# beacon.net
KiCad netlist of a schematic drawn in EAGLE
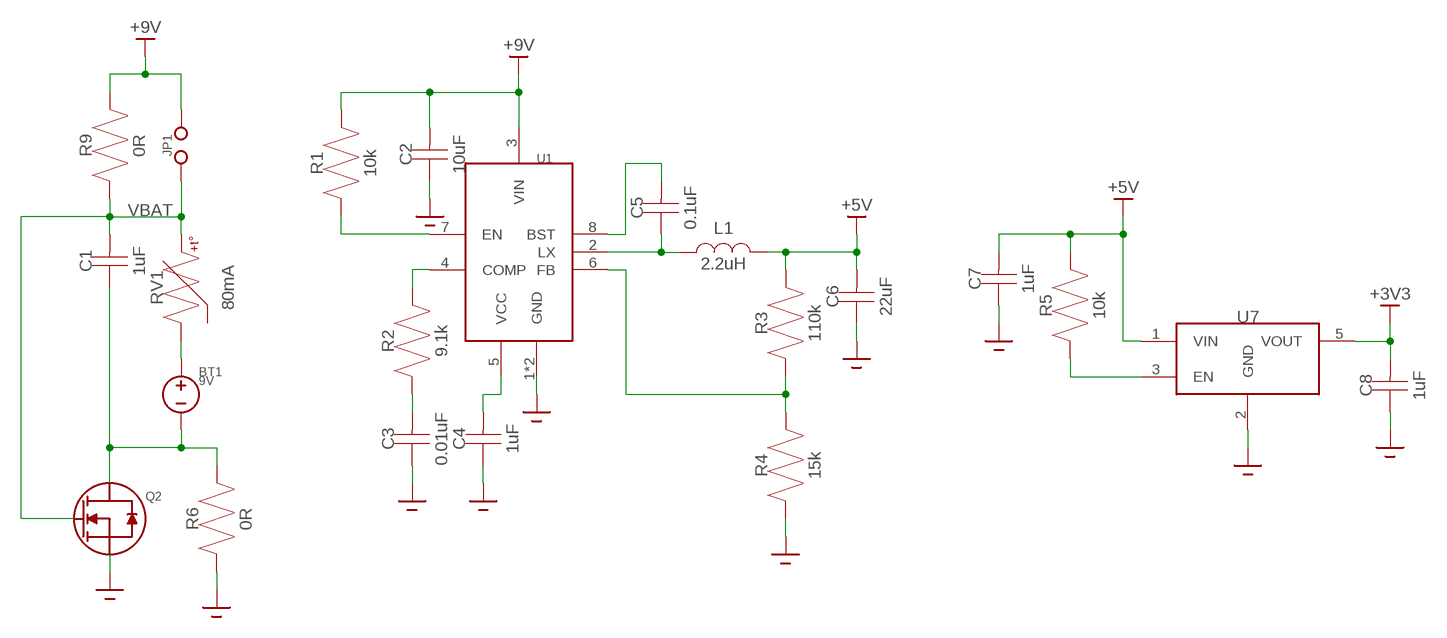
[diagram p0: schematic, sheet 1]
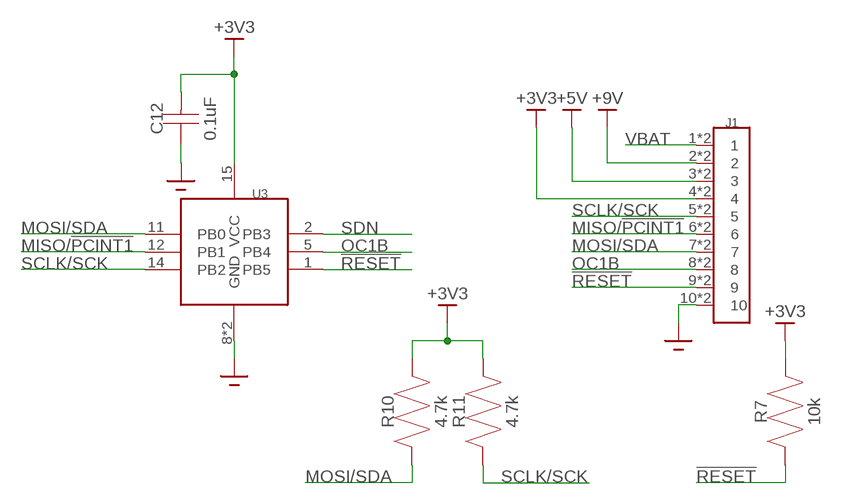
[diagram p1: schematic, sheet 2]
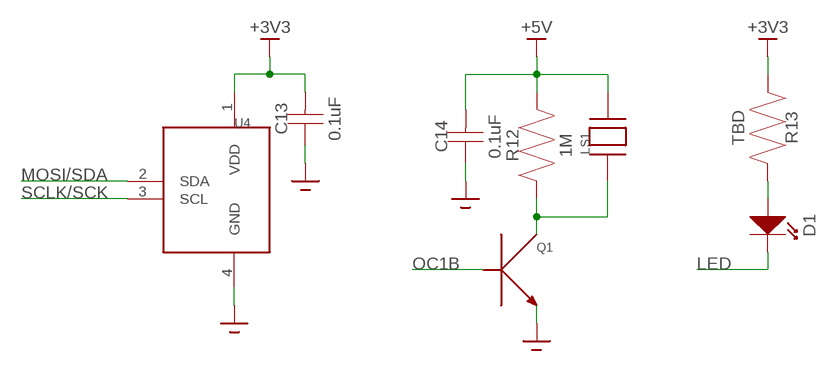
[diagram p2: schematic, sheet 3]
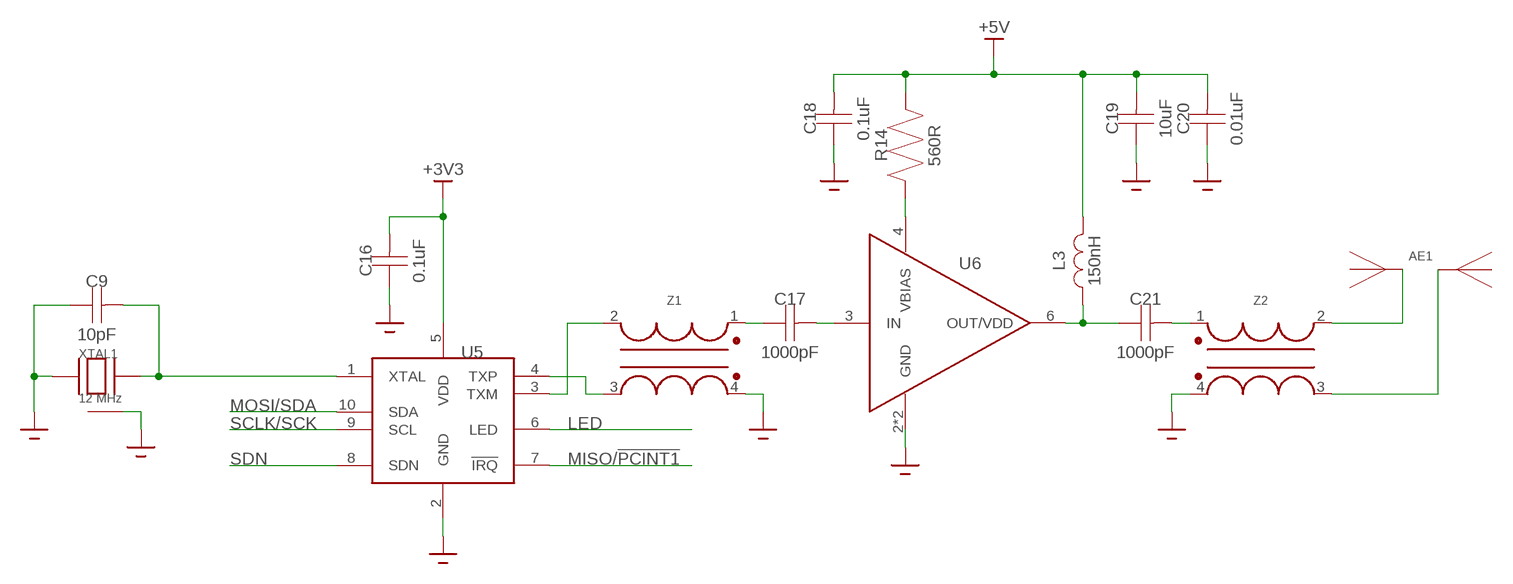
[diagram p3: schematic, sheet 4]

(export (version "E")
  (design (tool "Eeschema 10.0.6"))
  (components
    (comp (ref "AE1")
      (value "ANTENNA")
      (footprint "eagle-import:ANTENNA")
      (libsource (lib "eagle-import") (part "ANTENNA"))
    )
    (comp (ref "C9")
      (value "10pF")
      (footprint "eagle-import:0603")
      (libsource (lib "eagle-import") (part "CAPACITOR0603"))
    )
    (comp (ref "C16")
      (value "0.1uF")
      (footprint "eagle-import:0603")
      (libsource (lib "eagle-import") (part "CAPACITOR0603"))
    )
    (comp (ref "C17")
      (value "1000pF")
      (footprint "eagle-import:0402")
      (libsource (lib "eagle-import") (part "CAPACITOR0402"))
    )
    (comp (ref "C18")
      (value "0.1uF")
      (footprint "eagle-import:0603")
      (libsource (lib "eagle-import") (part "CAPACITOR0603"))
    )
    (comp (ref "C19")
      (value "10uF")
      (footprint "eagle-import:0603")
      (libsource (lib "eagle-import") (part "CAPACITOR0603"))
    )
    (comp (ref "C20")
      (value "0.01uF")
      (footprint "eagle-import:0603")
      (libsource (lib "eagle-import") (part "CAPACITOR0603"))
    )
    (comp (ref "C21")
      (value "1000pF")
      (footprint "eagle-import:0402")
      (libsource (lib "eagle-import") (part "CAPACITOR0402"))
    )
    (comp (ref "L3")
      (value "150nH")
      (footprint "eagle-import:0402")
      (libsource (lib "eagle-import") (part "INDUCTOR0402"))
    )
    (comp (ref "R14")
      (value "560R")
      (footprint "eagle-import:0603")
      (libsource (lib "eagle-import") (part "RESISTOR0603"))
    )
    (comp (ref "U5")
      (value "SI4012")
      (footprint "eagle-import:SI4012")
      (libsource (lib "eagle-import") (part "SI4012"))
    )
    (comp (ref "U6")
      (value "MAAL-010704")
      (footprint "eagle-import:MAAL-010704")
      (libsource (lib "eagle-import") (part "MAAL-010704"))
    )
    (comp (ref "XTAL1")
      (value "12 MHz")
      (footprint "eagle-import:RH100")
      (libsource (lib "eagle-import") (part "RH100"))
    )
    (comp (ref "Z1")
      (value "ABT-8")
      (footprint "eagle-import:ABT-8")
      (libsource (lib "eagle-import") (part "ABT-8"))
    )
    (comp (ref "Z2")
      (value "ABT-8")
      (footprint "eagle-import:ABT-8")
      (libsource (lib "eagle-import") (part "ABT-8"))
    )
    (comp (ref "BT1")
      (value "9V")
      (footprint "eagle-import:JUMPER")
      (libsource (lib "eagle-import") (part "BATTERY"))
    )
    (comp (ref "C1")
      (value "1uF")
      (footprint "eagle-import:0603")
      (libsource (lib "eagle-import") (part "CAPACITOR0603"))
    )
    (comp (ref "C2")
      (value "10uF")
      (footprint "eagle-import:0805")
      (libsource (lib "eagle-import") (part "CAPACITOR0805"))
    )
    (comp (ref "C3")
      (value "0.01uF")
      (footprint "eagle-import:0603")
      (libsource (lib "eagle-import") (part "CAPACITOR0603"))
    )
    (comp (ref "C4")
      (value "1uF")
      (footprint "eagle-import:0603")
      (libsource (lib "eagle-import") (part "CAPACITOR0603"))
    )
    (comp (ref "C5")
      (value "0.1uF")
      (footprint "eagle-import:0603")
      (libsource (lib "eagle-import") (part "CAPACITOR0603"))
    )
    (comp (ref "C6")
      (value "22uF")
      (footprint "eagle-import:0805")
      (libsource (lib "eagle-import") (part "CAPACITOR0805"))
    )
    (comp (ref "C7")
      (value "1uF")
      (footprint "eagle-import:0603")
      (libsource (lib "eagle-import") (part "CAPACITOR0603"))
    )
    (comp (ref "C8")
      (value "1uF")
      (footprint "eagle-import:0603")
      (libsource (lib "eagle-import") (part "CAPACITOR0603"))
    )
    (comp (ref "JP1")
      (value "JUMPER")
      (footprint "eagle-import:JUMPER")
      (libsource (lib "eagle-import") (part "JUMPER"))
    )
    (comp (ref "L1")
      (value "2.2uH")
      (footprint "eagle-import:0805")
      (libsource (lib "eagle-import") (part "INDUCTOR0805"))
    )
    (comp (ref "Q2")
      (value "DMG2302UK")
      (footprint "eagle-import:DMG2302UK")
      (libsource (lib "eagle-import") (part "DMG2302UK"))
    )
    (comp (ref "R1")
      (value "10k")
      (footprint "eagle-import:0603")
      (libsource (lib "eagle-import") (part "RESISTOR0603"))
    )
    (comp (ref "R2")
      (value "9.1k")
      (footprint "eagle-import:0603")
      (libsource (lib "eagle-import") (part "RESISTOR0603"))
    )
    (comp (ref "R3")
      (value "110k")
      (footprint "eagle-import:0603")
      (libsource (lib "eagle-import") (part "RESISTOR0603"))
    )
    (comp (ref "R4")
      (value "15k")
      (footprint "eagle-import:0603")
      (libsource (lib "eagle-import") (part "RESISTOR0603"))
    )
    (comp (ref "R5")
      (value "10k")
      (footprint "eagle-import:0603")
      (libsource (lib "eagle-import") (part "RESISTOR0603"))
    )
    (comp (ref "R6")
      (value "0R")
      (footprint "eagle-import:0805")
      (libsource (lib "eagle-import") (part "RESISTOR0805"))
    )
    (comp (ref "R9")
      (value "0R")
      (footprint "eagle-import:0805")
      (libsource (lib "eagle-import") (part "RESISTOR0805"))
    )
    (comp (ref "RV1")
      (value "80mA")
      (footprint "eagle-import:0603")
      (libsource (lib "eagle-import") (part "PTC0603"))
    )
    (comp (ref "U1")
      (value "AOZ6662DI")
      (footprint "eagle-import:AOZ6662DI")
      (libsource (lib "eagle-import") (part "AOZ6662DI"))
    )
    (comp (ref "U7")
      (value "MIC5504")
      (footprint "eagle-import:MIC5504")
      (libsource (lib "eagle-import") (part "MIC5504"))
    )
    (comp (ref "C12")
      (value "0.1uF")
      (footprint "eagle-import:0603")
      (libsource (lib "eagle-import") (part "CAPACITOR0603"))
    )
    (comp (ref "J1")
      (value "5-5530843-0MALE")
      (footprint "eagle-import:5-5530843-0-M")
      (libsource (lib "eagle-import") (part "5-5530843-0MALE"))
    )
    (comp (ref "R7")
      (value "10k")
      (footprint "eagle-import:0603")
      (libsource (lib "eagle-import") (part "RESISTOR0603"))
    )
    (comp (ref "R10")
      (value "4.7k")
      (footprint "eagle-import:0603")
      (libsource (lib "eagle-import") (part "RESISTOR0603"))
    )
    (comp (ref "R11")
      (value "4.7k")
      (footprint "eagle-import:0603")
      (libsource (lib "eagle-import") (part "RESISTOR0603"))
    )
    (comp (ref "U3")
      (value "ATTINY85")
      (footprint "eagle-import:ATTINY85")
      (libsource (lib "eagle-import") (part "ATTINY85"))
    )
    (comp (ref "C13")
      (value "0.1uF")
      (footprint "eagle-import:0603")
      (libsource (lib "eagle-import") (part "CAPACITOR0603"))
    )
    (comp (ref "C14")
      (value "0.1uF")
      (footprint "eagle-import:0603")
      (libsource (lib "eagle-import") (part "CAPACITOR0603"))
    )
    (comp (ref "D1")
      (value "LED")
      (footprint "eagle-import:0805")
      (libsource (lib "eagle-import") (part "LED"))
    )
    (comp (ref "LS1")
      (value "AT-1224-TWT-5V-2-R")
      (footprint "eagle-import:AT-1224-TWT-5V-2-R")
      (libsource (lib "eagle-import") (part "AT-1224-TWT-5V-2-R"))
    )
    (comp (ref "Q1")
      (value "MMBT3904")
      (footprint "eagle-import:MMBT3904")
      (libsource (lib "eagle-import") (part "MMBT3904"))
    )
    (comp (ref "R12")
      (value "1M")
      (footprint "eagle-import:0603")
      (libsource (lib "eagle-import") (part "RESISTOR0603"))
    )
    (comp (ref "R13")
      (value "TBD")
      (footprint "eagle-import:0603")
      (libsource (lib "eagle-import") (part "RESISTOR0603"))
    )
    (comp (ref "U4")
      (value "MS5637-02BA03")
      (footprint "eagle-import:MS5637-02BA03")
      (libsource (lib "eagle-import") (part "MS5637-02BA03"))
    )
  )
  (nets
    (net (code "1") (name "+3V3") (class "Default")
      (node (ref "C12") (pin "P$2") (pinfunction "P$2_P$2") (pintype "passive"))
      (node (ref "C13") (pin "P$2") (pinfunction "P$2_P$2") (pintype "passive"))
      (node (ref "C16") (pin "P$2") (pinfunction "P$2_P$2") (pintype "passive"))
      (node (ref "C8") (pin "P$2") (pinfunction "P$2_P$2") (pintype "passive"))
      (node (ref "J1") (pin "14") (pinfunction "4_14") (pintype "power_in"))
      (node (ref "J1") (pin "4") (pinfunction "4_4") (pintype "power_in"))
      (node (ref "R10") (pin "P$2") (pinfunction "P$2_P$2") (pintype "passive"))
      (node (ref "R11") (pin "P$2") (pinfunction "P$2_P$2") (pintype "passive"))
      (node (ref "R13") (pin "P$1") (pinfunction "P$1_P$1") (pintype "passive"))
      (node (ref "R7") (pin "P$2") (pinfunction "P$2_P$2") (pintype "passive"))
      (node (ref "U3") (pin "15") (pinfunction "VCC_15") (pintype "power_in"))
      (node (ref "U4") (pin "1") (pinfunction "VDD_1") (pintype "power_in"))
      (node (ref "U5") (pin "5") (pinfunction "VDD_5") (pintype "power_in"))
      (node (ref "U7") (pin "5") (pinfunction "VOUT_5") (pintype "power_in"))
    )
    (net (code "2") (name "+5V") (class "Default")
      (node (ref "C14") (pin "P$2") (pinfunction "P$2_P$2") (pintype "passive"))
      (node (ref "C18") (pin "P$2") (pinfunction "P$2_P$2") (pintype "passive"))
      (node (ref "C19") (pin "P$2") (pinfunction "P$2_P$2") (pintype "passive"))
      (node (ref "C20") (pin "P$2") (pinfunction "P$2_P$2") (pintype "passive"))
      (node (ref "C6") (pin "P$2") (pinfunction "P$2_P$2") (pintype "passive"))
      (node (ref "C7") (pin "P$2") (pinfunction "P$2_P$2") (pintype "passive"))
      (node (ref "J1") (pin "13") (pinfunction "3_13") (pintype "power_in"))
      (node (ref "J1") (pin "3") (pinfunction "3_3") (pintype "power_in"))
      (node (ref "L1") (pin "P$2") (pinfunction "P$2_P$2") (pintype "passive"))
      (node (ref "L3") (pin "2") (pinfunction "P$2_2") (pintype "passive"))
      (node (ref "LS1") (pin "2") (pinfunction "P$2_2") (pintype "passive"))
      (node (ref "R12") (pin "P$2") (pinfunction "P$2_P$2") (pintype "passive"))
      (node (ref "R14") (pin "P$2") (pinfunction "P$2_P$2") (pintype "passive"))
      (node (ref "R3") (pin "P$2") (pinfunction "P$2_P$2") (pintype "passive"))
      (node (ref "R5") (pin "P$2") (pinfunction "P$2_P$2") (pintype "passive"))
      (node (ref "U7") (pin "1") (pinfunction "VIN_1") (pintype "power_in"))
    )
    (net (code "3") (name "+9V") (class "Default")
      (node (ref "C2") (pin "P$2") (pinfunction "P$2_P$2") (pintype "passive"))
      (node (ref "J1") (pin "12") (pinfunction "2_12") (pintype "power_in"))
      (node (ref "J1") (pin "2") (pinfunction "2_2") (pintype "power_in"))
      (node (ref "JP1") (pin "2") (pinfunction "P$2_2") (pintype "passive"))
      (node (ref "R1") (pin "P$2") (pinfunction "P$2_P$2") (pintype "passive"))
      (node (ref "R9") (pin "P$2") (pinfunction "P$2_P$2") (pintype "passive"))
      (node (ref "U1") (pin "3") (pinfunction "VIN_3") (pintype "power_in"))
    )
    (net (code "4") (name "GND") (class "Default")
      (node (ref "C12") (pin "P$1") (pinfunction "P$1_P$1") (pintype "passive"))
      (node (ref "C13") (pin "P$1") (pinfunction "P$1_P$1") (pintype "passive"))
      (node (ref "C14") (pin "P$1") (pinfunction "P$1_P$1") (pintype "passive"))
      (node (ref "C16") (pin "P$1") (pinfunction "P$1_P$1") (pintype "passive"))
      (node (ref "C18") (pin "P$1") (pinfunction "P$1_P$1") (pintype "passive"))
      (node (ref "C19") (pin "P$1") (pinfunction "P$1_P$1") (pintype "passive"))
      (node (ref "C2") (pin "P$1") (pinfunction "P$1_P$1") (pintype "passive"))
      (node (ref "C20") (pin "P$1") (pinfunction "P$1_P$1") (pintype "passive"))
      (node (ref "C3") (pin "P$1") (pinfunction "P$1_P$1") (pintype "passive"))
      (node (ref "C4") (pin "P$1") (pinfunction "P$1_P$1") (pintype "passive"))
      (node (ref "C6") (pin "P$1") (pinfunction "P$1_P$1") (pintype "passive"))
      (node (ref "C7") (pin "P$1") (pinfunction "P$1_P$1") (pintype "passive"))
      (node (ref "C8") (pin "P$1") (pinfunction "P$1_P$1") (pintype "passive"))
      (node (ref "C9") (pin "P$1") (pinfunction "P$1_P$1") (pintype "passive"))
      (node (ref "J1") (pin "10") (pinfunction "10_10") (pintype "power_in"))
      (node (ref "J1") (pin "20") (pinfunction "10_20") (pintype "power_in"))
      (node (ref "Q1") (pin "2") (pinfunction "E_2") (pintype "bidirectional"))
      (node (ref "Q2") (pin "2") (pinfunction "S_2") (pintype "bidirectional"))
      (node (ref "R4") (pin "P$1") (pinfunction "P$1_P$1") (pintype "passive"))
      (node (ref "R6") (pin "P$1") (pinfunction "P$1_P$1") (pintype "passive"))
      (node (ref "U1") (pin "1") (pinfunction "GND_1") (pintype "passive"))
      (node (ref "U1") (pin "9") (pinfunction "GND_9") (pintype "passive"))
      (node (ref "U3") (pin "21") (pinfunction "GND_21") (pintype "passive"))
      (node (ref "U3") (pin "8") (pinfunction "GND_8") (pintype "passive"))
      (node (ref "U4") (pin "4") (pinfunction "GND_4") (pintype "passive"))
      (node (ref "U5") (pin "2") (pinfunction "GND_2") (pintype "passive"))
      (node (ref "U6") (pin "2") (pinfunction "GND_2") (pintype "passive"))
      (node (ref "U6") (pin "5") (pinfunction "GND_5") (pintype "passive"))
      (node (ref "U7") (pin "2") (pinfunction "GND_2") (pintype "passive"))
      (node (ref "XTAL1") (pin "1") (pinfunction "GND_1") (pintype "passive"))
      (node (ref "XTAL1") (pin "2") (pinfunction "P$1_2") (pintype "passive"))
      (node (ref "XTAL1") (pin "3") (pinfunction "GND_3") (pintype "passive"))
      (node (ref "Z1") (pin "4") (pinfunction "UN2_4") (pintype "bidirectional"))
      (node (ref "Z2") (pin "4") (pinfunction "UN2_4") (pintype "bidirectional"))
    )
    (net (code "5") (name "LED") (class "Default")
      (node (ref "D1") (pin "P$2") (pinfunction "OUT_P$2") (pintype "passive"))
      (node (ref "U5") (pin "6") (pinfunction "LED_6") (pintype "bidirectional"))
    )
    (net (code "6") (name "MISO{slash}~{PCINT1}") (class "Default")
      (node (ref "J1") (pin "16") (pinfunction "6_16") (pintype "power_in"))
      (node (ref "J1") (pin "6") (pinfunction "6_6") (pintype "power_in"))
      (node (ref "U3") (pin "12") (pinfunction "PB1_12") (pintype "bidirectional"))
      (node (ref "U5") (pin "7") (pinfunction "~{IRQ}_7") (pintype "bidirectional"))
    )
    (net (code "7") (name "MOSI{slash}SDA") (class "Default")
      (node (ref "J1") (pin "17") (pinfunction "7_17") (pintype "power_in"))
      (node (ref "J1") (pin "7") (pinfunction "7_7") (pintype "power_in"))
      (node (ref "R10") (pin "P$1") (pinfunction "P$1_P$1") (pintype "passive"))
      (node (ref "U3") (pin "11") (pinfunction "PB0_11") (pintype "bidirectional"))
      (node (ref "U4") (pin "2") (pinfunction "SDA_2") (pintype "bidirectional"))
      (node (ref "U5") (pin "10") (pinfunction "SDA_10") (pintype "bidirectional"))
    )
    (net (code "8") (name "Net-(BT1-P$1)") (class "Default")
      (node (ref "BT1") (pin "1") (pinfunction "P$1_1") (pintype "passive"))
      (node (ref "C1") (pin "P$1") (pinfunction "P$1_P$1") (pintype "passive"))
      (node (ref "Q2") (pin "3") (pinfunction "D_3") (pintype "bidirectional"))
      (node (ref "R6") (pin "P$2") (pinfunction "P$2_P$2") (pintype "passive"))
    )
    (net (code "9") (name "Net-(BT1-P$2)") (class "Default")
      (node (ref "BT1") (pin "2") (pinfunction "P$2_2") (pintype "power_in"))
      (node (ref "RV1") (pin "P$1") (pinfunction "P$1_P$1") (pintype "passive"))
    )
    (net (code "10") (name "Net-(C3-PadP$2)") (class "Default")
      (node (ref "C3") (pin "P$2") (pinfunction "P$2_P$2") (pintype "passive"))
      (node (ref "R2") (pin "P$1") (pinfunction "P$1_P$1") (pintype "passive"))
    )
    (net (code "11") (name "Net-(C17-P$1)") (class "Default")
      (node (ref "C17") (pin "1") (pinfunction "P$1_1") (pintype "passive"))
      (node (ref "Z1") (pin "1") (pinfunction "UN1_1") (pintype "bidirectional"))
    )
    (net (code "12") (name "Net-(C17-P$2)") (class "Default")
      (node (ref "C17") (pin "2") (pinfunction "P$2_2") (pintype "passive"))
      (node (ref "U6") (pin "3") (pinfunction "IN_3") (pintype "bidirectional"))
    )
    (net (code "13") (name "Net-(C21-P$1)") (class "Default")
      (node (ref "C21") (pin "1") (pinfunction "P$1_1") (pintype "passive"))
      (node (ref "L3") (pin "1") (pinfunction "P$1_1") (pintype "passive"))
      (node (ref "U6") (pin "6") (pinfunction "OUT/VDD_6") (pintype "bidirectional"))
    )
    (net (code "14") (name "Net-(C21-P$2)") (class "Default")
      (node (ref "C21") (pin "2") (pinfunction "P$2_2") (pintype "passive"))
      (node (ref "Z2") (pin "1") (pinfunction "UN1_1") (pintype "bidirectional"))
    )
    (net (code "15") (name "Net-(D1-IN)") (class "Default")
      (node (ref "D1") (pin "P$1") (pinfunction "IN_P$1") (pintype "passive"))
      (node (ref "R13") (pin "P$2") (pinfunction "P$2_P$2") (pintype "passive"))
    )
    (net (code "16") (name "Net-(LS1-P$1)") (class "Default")
      (node (ref "LS1") (pin "1") (pinfunction "P$1_1") (pintype "passive"))
      (node (ref "Q1") (pin "3") (pinfunction "C_3") (pintype "bidirectional"))
      (node (ref "R12") (pin "P$1") (pinfunction "P$1_P$1") (pintype "passive"))
    )
    (net (code "17") (name "Net-(U1-BST)") (class "Default")
      (node (ref "C5") (pin "P$2") (pinfunction "P$2_P$2") (pintype "passive"))
      (node (ref "U1") (pin "8") (pinfunction "BST_8") (pintype "passive"))
    )
    (net (code "18") (name "Net-(U1-COMP)") (class "Default")
      (node (ref "R2") (pin "P$2") (pinfunction "P$2_P$2") (pintype "passive"))
      (node (ref "U1") (pin "4") (pinfunction "COMP_4") (pintype "passive"))
    )
    (net (code "19") (name "Net-(U1-EN)") (class "Default")
      (node (ref "R1") (pin "P$1") (pinfunction "P$1_P$1") (pintype "passive"))
      (node (ref "U1") (pin "7") (pinfunction "EN_7") (pintype "input"))
    )
    (net (code "20") (name "Net-(U1-FB)") (class "Default")
      (node (ref "R3") (pin "P$1") (pinfunction "P$1_P$1") (pintype "passive"))
      (node (ref "R4") (pin "P$2") (pinfunction "P$2_P$2") (pintype "passive"))
      (node (ref "U1") (pin "6") (pinfunction "FB_6") (pintype "input"))
    )
    (net (code "21") (name "Net-(U1-LX)") (class "Default")
      (node (ref "C5") (pin "P$1") (pinfunction "P$1_P$1") (pintype "passive"))
      (node (ref "L1") (pin "P$1") (pinfunction "P$1_P$1") (pintype "passive"))
      (node (ref "U1") (pin "2") (pinfunction "LX_2") (pintype "output"))
    )
    (net (code "22") (name "Net-(U1-VCC)") (class "Default")
      (node (ref "C4") (pin "P$2") (pinfunction "P$2_P$2") (pintype "passive"))
      (node (ref "U1") (pin "5") (pinfunction "VCC_5") (pintype "passive"))
    )
    (net (code "23") (name "Net-(U5-TXM)") (class "Default")
      (node (ref "U5") (pin "3") (pinfunction "TXM_3") (pintype "bidirectional"))
      (node (ref "Z1") (pin "2") (pinfunction "BAL1_2") (pintype "bidirectional"))
    )
    (net (code "24") (name "Net-(U5-TXP)") (class "Default")
      (node (ref "U5") (pin "4") (pinfunction "TXP_4") (pintype "bidirectional"))
      (node (ref "Z1") (pin "3") (pinfunction "BAL2_3") (pintype "bidirectional"))
    )
    (net (code "25") (name "Net-(U5-XTAL)") (class "Default")
      (node (ref "C9") (pin "P$2") (pinfunction "P$2_P$2") (pintype "passive"))
      (node (ref "U5") (pin "1") (pinfunction "XTAL_1") (pintype "bidirectional"))
      (node (ref "XTAL1") (pin "4") (pinfunction "P$2_4") (pintype "passive"))
    )
    (net (code "26") (name "Net-(U6-VBIAS)") (class "Default")
      (node (ref "R14") (pin "P$1") (pinfunction "P$1_P$1") (pintype "passive"))
      (node (ref "U6") (pin "4") (pinfunction "VBIAS_4") (pintype "power_in"))
    )
    (net (code "27") (name "Net-(U7-EN)") (class "Default")
      (node (ref "R5") (pin "P$1") (pinfunction "P$1_P$1") (pintype "passive"))
      (node (ref "U7") (pin "3") (pinfunction "EN_3") (pintype "input"))
    )
    (net (code "28") (name "Net-(Z2-BAL1)") (class "Default")
      (node (ref "AE1") (pin "LB") (pinfunction "P$1_LB") (pintype "passive"))
      (node (ref "AE1") (pin "LT") (pinfunction "P$1_LT") (pintype "passive"))
      (node (ref "Z2") (pin "2") (pinfunction "BAL1_2") (pintype "bidirectional"))
    )
    (net (code "29") (name "Net-(Z2-BAL2)") (class "Default")
      (node (ref "AE1") (pin "RB") (pinfunction "P$2_RB") (pintype "passive"))
      (node (ref "AE1") (pin "RT") (pinfunction "P$2_RT") (pintype "passive"))
      (node (ref "Z2") (pin "3") (pinfunction "BAL2_3") (pintype "bidirectional"))
    )
    (net (code "30") (name "OC1B") (class "Default")
      (node (ref "J1") (pin "18") (pinfunction "8_18") (pintype "power_in"))
      (node (ref "J1") (pin "8") (pinfunction "8_8") (pintype "power_in"))
      (node (ref "Q1") (pin "1") (pinfunction "B_1") (pintype "bidirectional"))
      (node (ref "U3") (pin "5") (pinfunction "PB4_5") (pintype "bidirectional"))
    )
    (net (code "31") (name "SCLK{slash}SCK") (class "Default")
      (node (ref "J1") (pin "15") (pinfunction "5_15") (pintype "power_in"))
      (node (ref "J1") (pin "5") (pinfunction "5_5") (pintype "power_in"))
      (node (ref "R11") (pin "P$1") (pinfunction "P$1_P$1") (pintype "passive"))
      (node (ref "U3") (pin "14") (pinfunction "PB2_14") (pintype "bidirectional"))
      (node (ref "U4") (pin "3") (pinfunction "SCL_3") (pintype "bidirectional"))
      (node (ref "U5") (pin "9") (pinfunction "SCL_9") (pintype "bidirectional"))
    )
    (net (code "32") (name "SDN") (class "Default")
      (node (ref "U3") (pin "2") (pinfunction "PB3_2") (pintype "bidirectional"))
      (node (ref "U5") (pin "8") (pinfunction "SDN_8") (pintype "bidirectional"))
    )
    (net (code "33") (name "VBAT") (class "Default")
      (node (ref "C1") (pin "P$2") (pinfunction "P$2_P$2") (pintype "passive"))
      (node (ref "J1") (pin "1") (pinfunction "1_1") (pintype "power_in"))
      (node (ref "J1") (pin "11") (pinfunction "1_11") (pintype "power_in"))
      (node (ref "JP1") (pin "1") (pinfunction "P$1_1") (pintype "passive"))
      (node (ref "Q2") (pin "1") (pinfunction "G_1") (pintype "bidirectional"))
      (node (ref "R9") (pin "P$1") (pinfunction "P$1_P$1") (pintype "passive"))
      (node (ref "RV1") (pin "P$2") (pinfunction "P$2_P$2") (pintype "passive"))
    )
    (net (code "34") (name "~{RESET}") (class "Default")
      (node (ref "J1") (pin "19") (pinfunction "9_19") (pintype "power_in"))
      (node (ref "J1") (pin "9") (pinfunction "9_9") (pintype "power_in"))
      (node (ref "R7") (pin "P$1") (pinfunction "P$1_P$1") (pintype "passive"))
      (node (ref "U3") (pin "1") (pinfunction "PB5_1") (pintype "bidirectional"))
    )
  )
)
